# MTL_BaroTact1D_V4.net
KiCad netlist of a schematic drawn in EAGLE
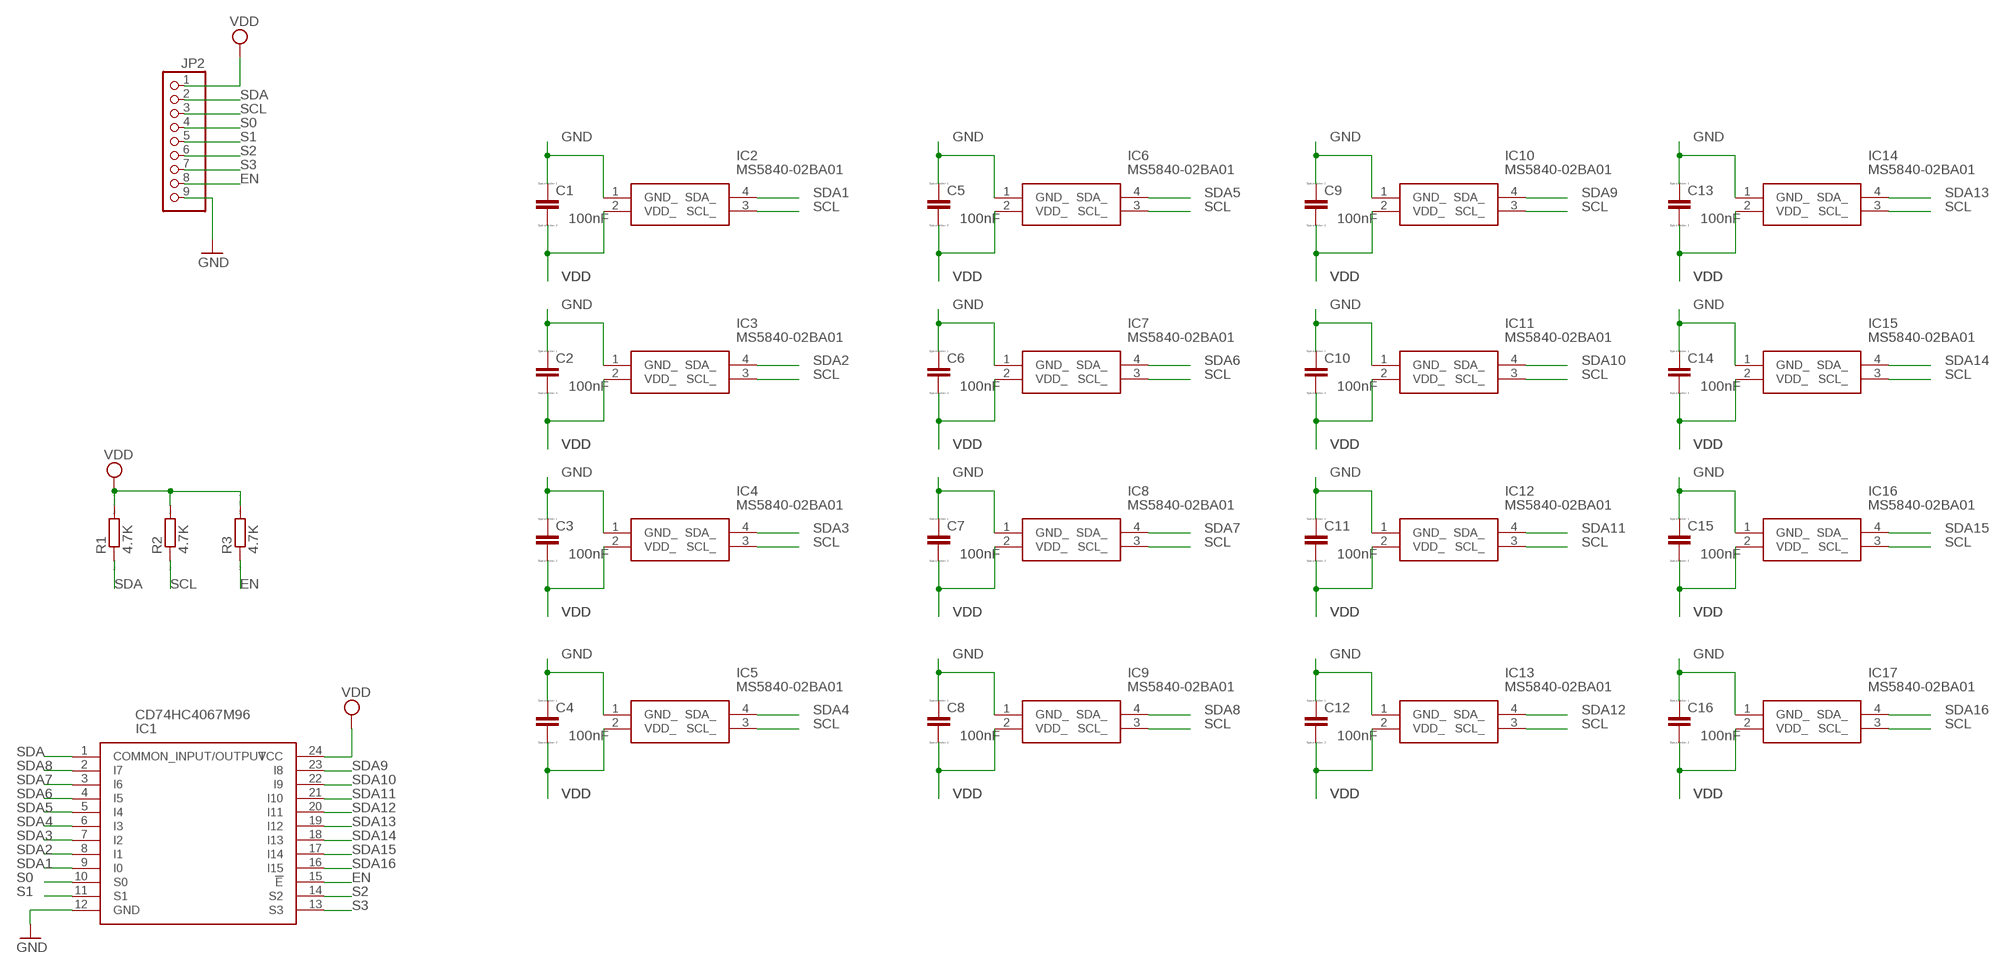
[diagram p0: schematic, sheet 1]

(export (version "E")
  (design (tool "Eeschema 10.0.6"))
  (components
    (comp (ref "C1")
      (value "100nF")
      (footprint "eagle-import:C0603")
      (libsource (lib "eagle-import") (part "CC0603"))
    )
    (comp (ref "C2")
      (value "100nF")
      (footprint "eagle-import:C0603")
      (libsource (lib "eagle-import") (part "CC0603"))
    )
    (comp (ref "C3")
      (value "100nF")
      (footprint "eagle-import:C0603")
      (libsource (lib "eagle-import") (part "CC0603"))
    )
    (comp (ref "C4")
      (value "100nF")
      (footprint "eagle-import:C0603")
      (libsource (lib "eagle-import") (part "CC0603"))
    )
    (comp (ref "C5")
      (value "100nF")
      (footprint "eagle-import:C0603")
      (libsource (lib "eagle-import") (part "CC0603"))
    )
    (comp (ref "C6")
      (value "100nF")
      (footprint "eagle-import:C0603")
      (libsource (lib "eagle-import") (part "CC0603"))
    )
    (comp (ref "C7")
      (value "100nF")
      (footprint "eagle-import:C0603")
      (libsource (lib "eagle-import") (part "CC0603"))
    )
    (comp (ref "C8")
      (value "100nF")
      (footprint "eagle-import:C0603")
      (libsource (lib "eagle-import") (part "CC0603"))
    )
    (comp (ref "C9")
      (value "100nF")
      (footprint "eagle-import:C0603")
      (libsource (lib "eagle-import") (part "CC0603"))
    )
    (comp (ref "C10")
      (value "100nF")
      (footprint "eagle-import:C0603")
      (libsource (lib "eagle-import") (part "CC0603"))
    )
    (comp (ref "C11")
      (value "100nF")
      (footprint "eagle-import:C0603")
      (libsource (lib "eagle-import") (part "CC0603"))
    )
    (comp (ref "C12")
      (value "100nF")
      (footprint "eagle-import:C0603")
      (libsource (lib "eagle-import") (part "CC0603"))
    )
    (comp (ref "C13")
      (value "100nF")
      (footprint "eagle-import:C0603")
      (libsource (lib "eagle-import") (part "CC0603"))
    )
    (comp (ref "C14")
      (value "100nF")
      (footprint "eagle-import:C0603")
      (libsource (lib "eagle-import") (part "CC0603"))
    )
    (comp (ref "C15")
      (value "100nF")
      (footprint "eagle-import:C0603")
      (libsource (lib "eagle-import") (part "CC0603"))
    )
    (comp (ref "C16")
      (value "100nF")
      (footprint "eagle-import:C0603")
      (libsource (lib "eagle-import") (part "CC0603"))
    )
    (comp (ref "IC1")
      (value "CD74HC4067M96")
      (footprint "eagle-import:SOIC127P1030X265-24N")
      (fields (field (name "MOUSER_PART_NUMBER") "595-CD74HC4067M96"))
      (libsource (lib "eagle-import") (part "CD74HC4067M96"))
    )
    (comp (ref "IC2")
      (value "MS5840-02BA01")
      (footprint "eagle-import:MS584002BA01")
      (fields (field (name "MOUSER_PART_NUMBER") "824-MS5840-02BA01"))
      (libsource (lib "eagle-import") (part "MS5840-02BA01"))
    )
    (comp (ref "IC3")
      (value "MS5840-02BA01")
      (footprint "eagle-import:MS584002BA01")
      (fields (field (name "MOUSER_PART_NUMBER") "824-MS5840-02BA01"))
      (libsource (lib "eagle-import") (part "MS5840-02BA01"))
    )
    (comp (ref "IC4")
      (value "MS5840-02BA01")
      (footprint "eagle-import:MS584002BA01")
      (fields (field (name "MOUSER_PART_NUMBER") "824-MS5840-02BA01"))
      (libsource (lib "eagle-import") (part "MS5840-02BA01"))
    )
    (comp (ref "IC5")
      (value "MS5840-02BA01")
      (footprint "eagle-import:MS584002BA01")
      (fields (field (name "MOUSER_PART_NUMBER") "824-MS5840-02BA01"))
      (libsource (lib "eagle-import") (part "MS5840-02BA01"))
    )
    (comp (ref "IC6")
      (value "MS5840-02BA01")
      (footprint "eagle-import:MS584002BA01")
      (fields (field (name "MOUSER_PART_NUMBER") "824-MS5840-02BA01"))
      (libsource (lib "eagle-import") (part "MS5840-02BA01"))
    )
    (comp (ref "IC7")
      (value "MS5840-02BA01")
      (footprint "eagle-import:MS584002BA01")
      (fields (field (name "MOUSER_PART_NUMBER") "824-MS5840-02BA01"))
      (libsource (lib "eagle-import") (part "MS5840-02BA01"))
    )
    (comp (ref "IC8")
      (value "MS5840-02BA01")
      (footprint "eagle-import:MS584002BA01")
      (fields (field (name "MOUSER_PART_NUMBER") "824-MS5840-02BA01"))
      (libsource (lib "eagle-import") (part "MS5840-02BA01"))
    )
    (comp (ref "IC9")
      (value "MS5840-02BA01")
      (footprint "eagle-import:MS584002BA01")
      (fields (field (name "MOUSER_PART_NUMBER") "824-MS5840-02BA01"))
      (libsource (lib "eagle-import") (part "MS5840-02BA01"))
    )
    (comp (ref "IC10")
      (value "MS5840-02BA01")
      (footprint "eagle-import:MS584002BA01")
      (fields (field (name "MOUSER_PART_NUMBER") "824-MS5840-02BA01"))
      (libsource (lib "eagle-import") (part "MS5840-02BA01"))
    )
    (comp (ref "IC11")
      (value "MS5840-02BA01")
      (footprint "eagle-import:MS584002BA01")
      (fields (field (name "MOUSER_PART_NUMBER") "824-MS5840-02BA01"))
      (libsource (lib "eagle-import") (part "MS5840-02BA01"))
    )
    (comp (ref "IC12")
      (value "MS5840-02BA01")
      (footprint "eagle-import:MS584002BA01")
      (fields (field (name "MOUSER_PART_NUMBER") "824-MS5840-02BA01"))
      (libsource (lib "eagle-import") (part "MS5840-02BA01"))
    )
    (comp (ref "IC13")
      (value "MS5840-02BA01")
      (footprint "eagle-import:MS584002BA01")
      (fields (field (name "MOUSER_PART_NUMBER") "824-MS5840-02BA01"))
      (libsource (lib "eagle-import") (part "MS5840-02BA01"))
    )
    (comp (ref "IC14")
      (value "MS5840-02BA01")
      (footprint "eagle-import:MS584002BA01")
      (fields (field (name "MOUSER_PART_NUMBER") "824-MS5840-02BA01"))
      (libsource (lib "eagle-import") (part "MS5840-02BA01"))
    )
    (comp (ref "IC15")
      (value "MS5840-02BA01")
      (footprint "eagle-import:MS584002BA01")
      (fields (field (name "MOUSER_PART_NUMBER") "824-MS5840-02BA01"))
      (libsource (lib "eagle-import") (part "MS5840-02BA01"))
    )
    (comp (ref "IC16")
      (value "MS5840-02BA01")
      (footprint "eagle-import:MS584002BA01")
      (fields (field (name "MOUSER_PART_NUMBER") "824-MS5840-02BA01"))
      (libsource (lib "eagle-import") (part "MS5840-02BA01"))
    )
    (comp (ref "IC17")
      (value "MS5840-02BA01")
      (footprint "eagle-import:MS584002BA01")
      (fields (field (name "MOUSER_PART_NUMBER") "824-MS5840-02BA01"))
      (libsource (lib "eagle-import") (part "MS5840-02BA01"))
    )
    (comp (ref "JP2")
      (value "PINHD-1X9")
      (footprint "eagle-import:1X09")
      (libsource (lib "eagle-import") (part "PINHD-1X9"))
    )
    (comp (ref "R1")
      (value "4.7K")
      (footprint "eagle-import:R0603")
      (libsource (lib "eagle-import") (part "RR0603"))
    )
    (comp (ref "R2")
      (value "4.7K")
      (footprint "eagle-import:R0603")
      (libsource (lib "eagle-import") (part "RR0603"))
    )
    (comp (ref "R3")
      (value "4.7K")
      (footprint "eagle-import:R0603")
      (libsource (lib "eagle-import") (part "RR0603"))
    )
  )
  (nets
    (net (code "1") (name "/EN") (class "Default")
      (node (ref "IC1") (pin "15") (pinfunction "~{E}_15") (pintype "bidirectional"))
      (node (ref "JP2") (pin "8") (pinfunction "8_8") (pintype "passive"))
      (node (ref "R3") (pin "1") (pinfunction "1_1") (pintype "passive"))
    )
    (net (code "2") (name "/S0") (class "Default")
      (node (ref "IC1") (pin "10") (pinfunction "S0_10") (pintype "bidirectional"))
      (node (ref "JP2") (pin "4") (pinfunction "4_4") (pintype "passive"))
    )
    (net (code "3") (name "/S1") (class "Default")
      (node (ref "IC1") (pin "11") (pinfunction "S1_11") (pintype "bidirectional"))
      (node (ref "JP2") (pin "5") (pinfunction "5_5") (pintype "passive"))
    )
    (net (code "4") (name "/S2") (class "Default")
      (node (ref "IC1") (pin "14") (pinfunction "S2_14") (pintype "bidirectional"))
      (node (ref "JP2") (pin "6") (pinfunction "6_6") (pintype "passive"))
    )
    (net (code "5") (name "/S3") (class "Default")
      (node (ref "IC1") (pin "13") (pinfunction "S3_13") (pintype "bidirectional"))
      (node (ref "JP2") (pin "7") (pinfunction "7_7") (pintype "passive"))
    )
    (net (code "6") (name "/SCL") (class "Default")
      (node (ref "IC10") (pin "3") (pinfunction "SCL__3") (pintype "bidirectional"))
      (node (ref "IC11") (pin "3") (pinfunction "SCL__3") (pintype "bidirectional"))
      (node (ref "IC12") (pin "3") (pinfunction "SCL__3") (pintype "bidirectional"))
      (node (ref "IC13") (pin "3") (pinfunction "SCL__3") (pintype "bidirectional"))
      (node (ref "IC14") (pin "3") (pinfunction "SCL__3") (pintype "bidirectional"))
      (node (ref "IC15") (pin "3") (pinfunction "SCL__3") (pintype "bidirectional"))
      (node (ref "IC16") (pin "3") (pinfunction "SCL__3") (pintype "bidirectional"))
      (node (ref "IC17") (pin "3") (pinfunction "SCL__3") (pintype "bidirectional"))
      (node (ref "IC2") (pin "3") (pinfunction "SCL__3") (pintype "bidirectional"))
      (node (ref "IC3") (pin "3") (pinfunction "SCL__3") (pintype "bidirectional"))
      (node (ref "IC4") (pin "3") (pinfunction "SCL__3") (pintype "bidirectional"))
      (node (ref "IC5") (pin "3") (pinfunction "SCL__3") (pintype "bidirectional"))
      (node (ref "IC6") (pin "3") (pinfunction "SCL__3") (pintype "bidirectional"))
      (node (ref "IC7") (pin "3") (pinfunction "SCL__3") (pintype "bidirectional"))
      (node (ref "IC8") (pin "3") (pinfunction "SCL__3") (pintype "bidirectional"))
      (node (ref "IC9") (pin "3") (pinfunction "SCL__3") (pintype "bidirectional"))
      (node (ref "JP2") (pin "3") (pinfunction "3_3") (pintype "passive"))
      (node (ref "R2") (pin "1") (pinfunction "1_1") (pintype "passive"))
    )
    (net (code "7") (name "/SDA") (class "Default")
      (node (ref "IC1") (pin "1") (pinfunction "COMMON_INPUT/OUTPUT_1") (pintype "bidirectional"))
      (node (ref "JP2") (pin "2") (pinfunction "2_2") (pintype "passive"))
      (node (ref "R1") (pin "1") (pinfunction "1_1") (pintype "passive"))
    )
    (net (code "8") (name "/SDA1") (class "Default")
      (node (ref "IC1") (pin "9") (pinfunction "I0_9") (pintype "bidirectional"))
      (node (ref "IC2") (pin "4") (pinfunction "SDA__4") (pintype "bidirectional"))
    )
    (net (code "9") (name "/SDA2") (class "Default")
      (node (ref "IC1") (pin "8") (pinfunction "I1_8") (pintype "bidirectional"))
      (node (ref "IC3") (pin "4") (pinfunction "SDA__4") (pintype "bidirectional"))
    )
    (net (code "10") (name "/SDA3") (class "Default")
      (node (ref "IC1") (pin "7") (pinfunction "I2_7") (pintype "bidirectional"))
      (node (ref "IC4") (pin "4") (pinfunction "SDA__4") (pintype "bidirectional"))
    )
    (net (code "11") (name "/SDA4") (class "Default")
      (node (ref "IC1") (pin "6") (pinfunction "I3_6") (pintype "bidirectional"))
      (node (ref "IC5") (pin "4") (pinfunction "SDA__4") (pintype "bidirectional"))
    )
    (net (code "12") (name "/SDA5") (class "Default")
      (node (ref "IC1") (pin "5") (pinfunction "I4_5") (pintype "bidirectional"))
      (node (ref "IC6") (pin "4") (pinfunction "SDA__4") (pintype "bidirectional"))
    )
    (net (code "13") (name "/SDA6") (class "Default")
      (node (ref "IC1") (pin "4") (pinfunction "I5_4") (pintype "bidirectional"))
      (node (ref "IC7") (pin "4") (pinfunction "SDA__4") (pintype "bidirectional"))
    )
    (net (code "14") (name "/SDA7") (class "Default")
      (node (ref "IC1") (pin "3") (pinfunction "I6_3") (pintype "bidirectional"))
      (node (ref "IC8") (pin "4") (pinfunction "SDA__4") (pintype "bidirectional"))
    )
    (net (code "15") (name "/SDA8") (class "Default")
      (node (ref "IC1") (pin "2") (pinfunction "I7_2") (pintype "bidirectional"))
      (node (ref "IC9") (pin "4") (pinfunction "SDA__4") (pintype "bidirectional"))
    )
    (net (code "16") (name "/SDA9") (class "Default")
      (node (ref "IC1") (pin "23") (pinfunction "I8_23") (pintype "bidirectional"))
      (node (ref "IC10") (pin "4") (pinfunction "SDA__4") (pintype "bidirectional"))
    )
    (net (code "17") (name "/SDA10") (class "Default")
      (node (ref "IC1") (pin "22") (pinfunction "I9_22") (pintype "bidirectional"))
      (node (ref "IC11") (pin "4") (pinfunction "SDA__4") (pintype "bidirectional"))
    )
    (net (code "18") (name "/SDA11") (class "Default")
      (node (ref "IC1") (pin "21") (pinfunction "I10_21") (pintype "bidirectional"))
      (node (ref "IC12") (pin "4") (pinfunction "SDA__4") (pintype "bidirectional"))
    )
    (net (code "19") (name "/SDA12") (class "Default")
      (node (ref "IC1") (pin "20") (pinfunction "I11_20") (pintype "bidirectional"))
      (node (ref "IC13") (pin "4") (pinfunction "SDA__4") (pintype "bidirectional"))
    )
    (net (code "20") (name "/SDA13") (class "Default")
      (node (ref "IC1") (pin "19") (pinfunction "I12_19") (pintype "bidirectional"))
      (node (ref "IC14") (pin "4") (pinfunction "SDA__4") (pintype "bidirectional"))
    )
    (net (code "21") (name "/SDA14") (class "Default")
      (node (ref "IC1") (pin "18") (pinfunction "I13_18") (pintype "bidirectional"))
      (node (ref "IC15") (pin "4") (pinfunction "SDA__4") (pintype "bidirectional"))
    )
    (net (code "22") (name "/SDA15") (class "Default")
      (node (ref "IC1") (pin "17") (pinfunction "I14_17") (pintype "bidirectional"))
      (node (ref "IC16") (pin "4") (pinfunction "SDA__4") (pintype "bidirectional"))
    )
    (net (code "23") (name "/SDA16") (class "Default")
      (node (ref "IC1") (pin "16") (pinfunction "I15_16") (pintype "bidirectional"))
      (node (ref "IC17") (pin "4") (pinfunction "SDA__4") (pintype "bidirectional"))
    )
    (net (code "24") (name "GND") (class "Default")
      (node (ref "C1") (pin "1") (pinfunction "1_1") (pintype "passive"))
      (node (ref "C10") (pin "1") (pinfunction "1_1") (pintype "passive"))
      (node (ref "C11") (pin "1") (pinfunction "1_1") (pintype "passive"))
      (node (ref "C12") (pin "1") (pinfunction "1_1") (pintype "passive"))
      (node (ref "C13") (pin "1") (pinfunction "1_1") (pintype "passive"))
      (node (ref "C14") (pin "1") (pinfunction "1_1") (pintype "passive"))
      (node (ref "C15") (pin "1") (pinfunction "1_1") (pintype "passive"))
      (node (ref "C16") (pin "1") (pinfunction "1_1") (pintype "passive"))
      (node (ref "C2") (pin "1") (pinfunction "1_1") (pintype "passive"))
      (node (ref "C3") (pin "1") (pinfunction "1_1") (pintype "passive"))
      (node (ref "C4") (pin "1") (pinfunction "1_1") (pintype "passive"))
      (node (ref "C5") (pin "1") (pinfunction "1_1") (pintype "passive"))
      (node (ref "C6") (pin "1") (pinfunction "1_1") (pintype "passive"))
      (node (ref "C7") (pin "1") (pinfunction "1_1") (pintype "passive"))
      (node (ref "C8") (pin "1") (pinfunction "1_1") (pintype "passive"))
      (node (ref "C9") (pin "1") (pinfunction "1_1") (pintype "passive"))
      (node (ref "IC1") (pin "12") (pinfunction "GND_12") (pintype "bidirectional"))
      (node (ref "IC10") (pin "1") (pinfunction "GND__1") (pintype "bidirectional"))
      (node (ref "IC11") (pin "1") (pinfunction "GND__1") (pintype "bidirectional"))
      (node (ref "IC12") (pin "1") (pinfunction "GND__1") (pintype "bidirectional"))
      (node (ref "IC13") (pin "1") (pinfunction "GND__1") (pintype "bidirectional"))
      (node (ref "IC14") (pin "1") (pinfunction "GND__1") (pintype "bidirectional"))
      (node (ref "IC15") (pin "1") (pinfunction "GND__1") (pintype "bidirectional"))
      (node (ref "IC16") (pin "1") (pinfunction "GND__1") (pintype "bidirectional"))
      (node (ref "IC17") (pin "1") (pinfunction "GND__1") (pintype "bidirectional"))
      (node (ref "IC2") (pin "1") (pinfunction "GND__1") (pintype "bidirectional"))
      (node (ref "IC3") (pin "1") (pinfunction "GND__1") (pintype "bidirectional"))
      (node (ref "IC4") (pin "1") (pinfunction "GND__1") (pintype "bidirectional"))
      (node (ref "IC5") (pin "1") (pinfunction "GND__1") (pintype "bidirectional"))
      (node (ref "IC6") (pin "1") (pinfunction "GND__1") (pintype "bidirectional"))
      (node (ref "IC7") (pin "1") (pinfunction "GND__1") (pintype "bidirectional"))
      (node (ref "IC8") (pin "1") (pinfunction "GND__1") (pintype "bidirectional"))
      (node (ref "IC9") (pin "1") (pinfunction "GND__1") (pintype "bidirectional"))
      (node (ref "JP2") (pin "9") (pinfunction "9_9") (pintype "passive"))
    )
    (net (code "25") (name "VDD") (class "Default")
      (node (ref "C1") (pin "2") (pinfunction "2_2") (pintype "passive"))
      (node (ref "C10") (pin "2") (pinfunction "2_2") (pintype "passive"))
      (node (ref "C11") (pin "2") (pinfunction "2_2") (pintype "passive"))
      (node (ref "C12") (pin "2") (pinfunction "2_2") (pintype "passive"))
      (node (ref "C13") (pin "2") (pinfunction "2_2") (pintype "passive"))
      (node (ref "C14") (pin "2") (pinfunction "2_2") (pintype "passive"))
      (node (ref "C15") (pin "2") (pinfunction "2_2") (pintype "passive"))
      (node (ref "C16") (pin "2") (pinfunction "2_2") (pintype "passive"))
      (node (ref "C2") (pin "2") (pinfunction "2_2") (pintype "passive"))
      (node (ref "C3") (pin "2") (pinfunction "2_2") (pintype "passive"))
      (node (ref "C4") (pin "2") (pinfunction "2_2") (pintype "passive"))
      (node (ref "C5") (pin "2") (pinfunction "2_2") (pintype "passive"))
      (node (ref "C6") (pin "2") (pinfunction "2_2") (pintype "passive"))
      (node (ref "C7") (pin "2") (pinfunction "2_2") (pintype "passive"))
      (node (ref "C8") (pin "2") (pinfunction "2_2") (pintype "passive"))
      (node (ref "C9") (pin "2") (pinfunction "2_2") (pintype "passive"))
      (node (ref "IC1") (pin "24") (pinfunction "VCC_24") (pintype "bidirectional"))
      (node (ref "IC10") (pin "2") (pinfunction "VDD__2") (pintype "bidirectional"))
      (node (ref "IC11") (pin "2") (pinfunction "VDD__2") (pintype "bidirectional"))
      (node (ref "IC12") (pin "2") (pinfunction "VDD__2") (pintype "bidirectional"))
      (node (ref "IC13") (pin "2") (pinfunction "VDD__2") (pintype "bidirectional"))
      (node (ref "IC14") (pin "2") (pinfunction "VDD__2") (pintype "bidirectional"))
      (node (ref "IC15") (pin "2") (pinfunction "VDD__2") (pintype "bidirectional"))
      (node (ref "IC16") (pin "2") (pinfunction "VDD__2") (pintype "bidirectional"))
      (node (ref "IC17") (pin "2") (pinfunction "VDD__2") (pintype "bidirectional"))
      (node (ref "IC2") (pin "2") (pinfunction "VDD__2") (pintype "bidirectional"))
      (node (ref "IC3") (pin "2") (pinfunction "VDD__2") (pintype "bidirectional"))
      (node (ref "IC4") (pin "2") (pinfunction "VDD__2") (pintype "bidirectional"))
      (node (ref "IC5") (pin "2") (pinfunction "VDD__2") (pintype "bidirectional"))
      (node (ref "IC6") (pin "2") (pinfunction "VDD__2") (pintype "bidirectional"))
      (node (ref "IC7") (pin "2") (pinfunction "VDD__2") (pintype "bidirectional"))
      (node (ref "IC8") (pin "2") (pinfunction "VDD__2") (pintype "bidirectional"))
      (node (ref "IC9") (pin "2") (pinfunction "VDD__2") (pintype "bidirectional"))
      (node (ref "JP2") (pin "1") (pinfunction "1_1") (pintype "passive"))
      (node (ref "R1") (pin "2") (pinfunction "2_2") (pintype "passive"))
      (node (ref "R2") (pin "2") (pinfunction "2_2") (pintype "passive"))
      (node (ref "R3") (pin "2") (pinfunction "2_2") (pintype "passive"))
    )
  )
)
